# TLV3501.net
KiCad netlist of a schematic drawn in EasyEDA Pro
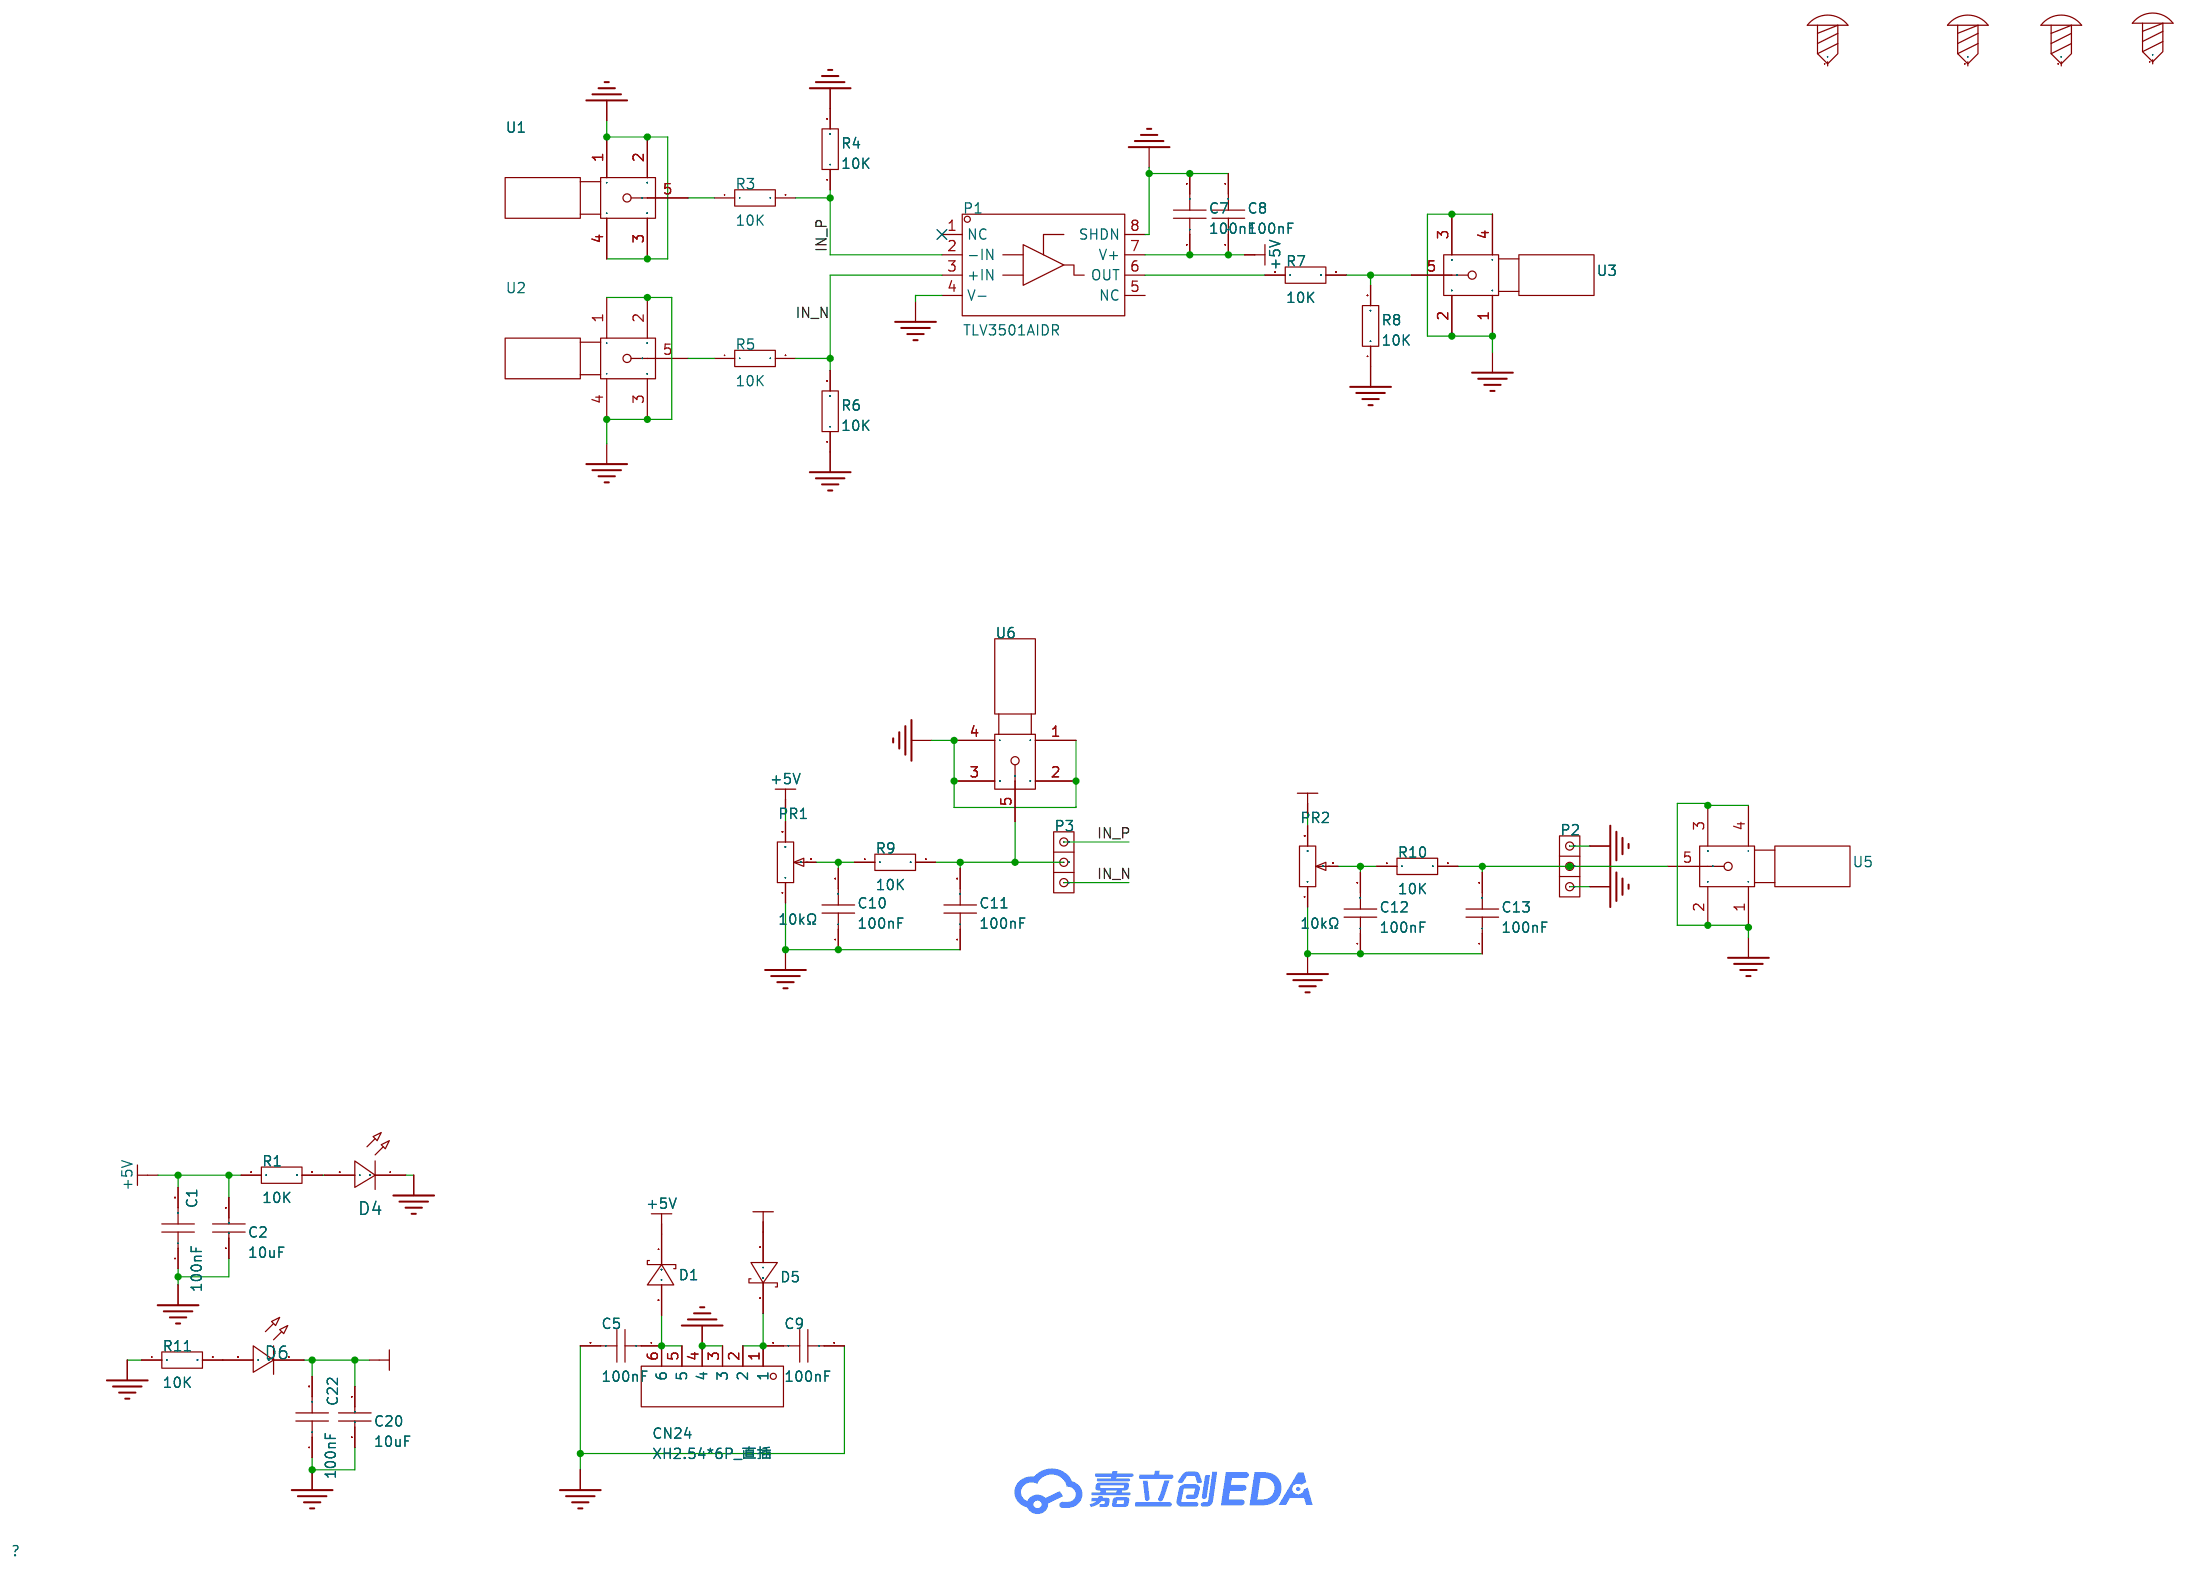
[diagram p0: schematic sheet]

(export (version "E")
  (design (tool "Eeschema 10.0.6"))
  (components
    (comp (ref "C1")
      (value "100nF")
      (footprint "easyedapro:C0805")
      (libsource (lib "easyedapro") (part "CapAcitance"))
    )
    (comp (ref "C2")
      (value "10uF")
      (footprint "easyedapro:C1210")
      (description "容值:10uF;精度:±10%;额定电压:25V;材质(温度系数):X7R;")
      (fields
        (field (name "Manufacturer Part") "CL32B106KAJNNNE")
        (field (name "Manufacturer") "SAMSUNG(三星)")
      )
      (libsource (lib "easyedapro") (part "CL32B106KAJNNNE"))
    )
    (comp (ref "C5")
      (value "100nF")
      (footprint "easyedapro:C0805")
      (libsource (lib "easyedapro") (part "CapAcitance"))
    )
    (comp (ref "C7")
      (value "100nF")
      (footprint "easyedapro:C0805")
      (libsource (lib "easyedapro") (part "CapAcitance"))
    )
    (comp (ref "C8")
      (value "100nF")
      (footprint "easyedapro:C0805")
      (libsource (lib "easyedapro") (part "CapAcitance"))
    )
    (comp (ref "C9")
      (value "100nF")
      (footprint "easyedapro:C0805")
      (libsource (lib "easyedapro") (part "CapAcitance"))
    )
    (comp (ref "C10")
      (value "100nF")
      (footprint "easyedapro:C0805")
      (libsource (lib "easyedapro") (part "CapAcitance"))
    )
    (comp (ref "C11")
      (value "100nF")
      (footprint "easyedapro:C0805")
      (libsource (lib "easyedapro") (part "CapAcitance"))
    )
    (comp (ref "C12")
      (value "100nF")
      (footprint "easyedapro:C0805")
      (libsource (lib "easyedapro") (part "CapAcitance"))
    )
    (comp (ref "C13")
      (value "100nF")
      (footprint "easyedapro:C0805")
      (libsource (lib "easyedapro") (part "CapAcitance"))
    )
    (comp (ref "C20")
      (value "10uF")
      (footprint "easyedapro:C1210")
      (description "容值:10uF;精度:±10%;额定电压:25V;材质(温度系数):X7R;")
      (fields
        (field (name "Manufacturer Part") "CL32B106KAJNNNE")
        (field (name "Manufacturer") "SAMSUNG(三星)")
      )
      (libsource (lib "easyedapro") (part "CL32B106KAJNNNE"))
    )
    (comp (ref "C22")
      (value "100nF")
      (footprint "easyedapro:C0805")
      (libsource (lib "easyedapro") (part "CapAcitance"))
    )
    (comp (ref "CN24")
      (value "XH2.54*6P_直插")
      (footprint "easyedapro:CONN-TH_XH2.54-6P")
      (libsource (lib "easyedapro") (part "XH2.54*6P_直插"))
    )
    (comp (ref "D1")
      (value "SD103AWS")
      (footprint "easyedapro:SOD-323_L1.8-W1.3-LS2.5-RD")
      (description "正向压降(Vf):600mV@200mA;直流反向耐压(Vr):40V;整流电流:350mA;")
      (fields (field (name "Manufacturer") "Hottech(合科泰)"))
      (libsource (lib "easyedapro") (part "SD103AWS_C181207"))
    )
    (comp (ref "D4")
      (value "~")
      (footprint "easyedapro:LED_0805")
      (libsource (lib "easyedapro") (part "LED_R"))
    )
    (comp (ref "D5")
      (value "SD103AWS")
      (footprint "easyedapro:SOD-323_L1.8-W1.3-LS2.5-RD")
      (description "正向压降(Vf):600mV@200mA;直流反向耐压(Vr):40V;整流电流:350mA;")
      (fields (field (name "Manufacturer") "Hottech(合科泰)"))
      (libsource (lib "easyedapro") (part "SD103AWS_C181207"))
    )
    (comp (ref "D6")
      (value "~")
      (footprint "easyedapro:LED_0805")
      (libsource (lib "easyedapro") (part "LED_R"))
    )
    (comp (ref "P1")
      (value "TLV3501AIDR")
      (footprint "easyedapro:SOP-8_L4.9-W3.9-P1.27-LS6.0-BL")
      (description "输入失调电压(Vos):6.5mV;输入偏置电流(Ib):10pA;")
      (fields (field (name "Manufacturer") "TI(德州仪器)"))
      (libsource (lib "easyedapro") (part "TLV3501AIDR"))
    )
    (comp (ref "P2") (value "~") (footprint "easyedapro:1*3跳线") (libsource (lib "easyedapro") (part "1*3跳线")))
    (comp (ref "P3") (value "~") (footprint "easyedapro:1*3跳线") (libsource (lib "easyedapro") (part "1*3跳线")))
    (comp (ref "PR1")
      (value "10kΩ")
      (footprint "easyedapro:R_3296")
      (libsource (lib "easyedapro") (part "R_3296"))
    )
    (comp (ref "PR2")
      (value "10kΩ")
      (footprint "easyedapro:R_3296")
      (libsource (lib "easyedapro") (part "R_3296"))
    )
    (comp (ref "R1") (value "10K") (footprint "easyedapro:R0805") (libsource (lib "easyedapro") (part "电阻")))
    (comp (ref "R3") (value "10K") (footprint "easyedapro:R0805") (libsource (lib "easyedapro") (part "电阻")))
    (comp (ref "R4") (value "10K") (footprint "easyedapro:R0805") (libsource (lib "easyedapro") (part "电阻")))
    (comp (ref "R5") (value "10K") (footprint "easyedapro:R0805") (libsource (lib "easyedapro") (part "电阻")))
    (comp (ref "R6") (value "10K") (footprint "easyedapro:R0805") (libsource (lib "easyedapro") (part "电阻")))
    (comp (ref "R7") (value "10K") (footprint "easyedapro:R0805") (libsource (lib "easyedapro") (part "电阻")))
    (comp (ref "R8") (value "10K") (footprint "easyedapro:R0805") (libsource (lib "easyedapro") (part "电阻")))
    (comp (ref "R9") (value "10K") (footprint "easyedapro:R0805") (libsource (lib "easyedapro") (part "电阻")))
    (comp (ref "R10") (value "10K") (footprint "easyedapro:R0805") (libsource (lib "easyedapro") (part "电阻")))
    (comp (ref "R11") (value "10K") (footprint "easyedapro:R0805") (libsource (lib "easyedapro") (part "电阻")))
    (comp (ref "SCREW1")
      (value "~")
      (footprint "easyedapro:M2螺丝")
      (libsource (lib "easyedapro") (part "螺丝孔"))
    )
    (comp (ref "SCREW2")
      (value "~")
      (footprint "easyedapro:M2螺丝")
      (libsource (lib "easyedapro") (part "螺丝孔"))
    )
    (comp (ref "SCREW3")
      (value "~")
      (footprint "easyedapro:M2螺丝")
      (libsource (lib "easyedapro") (part "螺丝孔"))
    )
    (comp (ref "SCREW4")
      (value "~")
      (footprint "easyedapro:M2螺丝")
      (libsource (lib "easyedapro") (part "螺丝孔"))
    )
    (comp (ref "U1") (value "~") (footprint "easyedapro:SMA") (libsource (lib "easyedapro") (part "SMA")))
    (comp (ref "U2") (value "~") (footprint "easyedapro:SMA") (libsource (lib "easyedapro") (part "SMA")))
    (comp (ref "U3") (value "~") (footprint "easyedapro:SMA") (libsource (lib "easyedapro") (part "SMA")))
    (comp (ref "U5") (value "~") (footprint "easyedapro:SMA") (libsource (lib "easyedapro") (part "SMA")))
    (comp (ref "U6") (value "~") (footprint "easyedapro:SMA") (libsource (lib "easyedapro") (part "SMA")))
  )
  (nets
    (net (code "1") (name "+5V") (class "Default")
      (node (ref "C1") (pin "2") (pinfunction "2_2") (pintype "input"))
      (node (ref "C2") (pin "2") (pinfunction "2_2") (pintype "input"))
      (node (ref "C7") (pin "2") (pinfunction "2_2") (pintype "input"))
      (node (ref "C8") (pin "2") (pinfunction "2_2") (pintype "input"))
      (node (ref "D1") (pin "1") (pinfunction "C_1") (pintype "unspecified"))
      (node (ref "P1") (pin "7") (pinfunction "V+_7") (pintype "unspecified"))
      (node (ref "PR1") (pin "3") (pinfunction "3_3") (pintype "input"))
      (node (ref "R1") (pin "1") (pinfunction "1_1") (pintype "input"))
    )
    (net (code "2") (name "-5V") (class "Default")
      (node (ref "C20") (pin "2") (pinfunction "2_2") (pintype "input"))
      (node (ref "C22") (pin "2") (pinfunction "2_2") (pintype "input"))
      (node (ref "D5") (pin "2") (pinfunction "A_2") (pintype "unspecified"))
      (node (ref "D6") (pin "1") (pinfunction "C_1") (pintype "input"))
      (node (ref "PR2") (pin "3") (pinfunction "3_3") (pintype "input"))
    )
    (net (code "3") (name "/IN_N") (class "Default")
      (node (ref "P1") (pin "3") (pinfunction "+IN_3") (pintype "unspecified"))
      (node (ref "P3") (pin "3") (pinfunction "3_3") (pintype "input"))
      (node (ref "R5") (pin "2") (pinfunction "2_2") (pintype "input"))
      (node (ref "R6") (pin "2") (pinfunction "2_2") (pintype "input"))
    )
    (net (code "4") (name "/IN_P") (class "Default")
      (node (ref "P1") (pin "2") (pinfunction "-IN_2") (pintype "unspecified"))
      (node (ref "P3") (pin "1") (pinfunction "1_1") (pintype "input"))
      (node (ref "R3") (pin "2") (pinfunction "2_2") (pintype "input"))
      (node (ref "R4") (pin "1") (pinfunction "1_1") (pintype "input"))
    )
    (net (code "5") (name "GND") (class "Default")
      (node (ref "C1") (pin "1") (pinfunction "1_1") (pintype "input"))
      (node (ref "C10") (pin "1") (pinfunction "1_1") (pintype "input"))
      (node (ref "C11") (pin "1") (pinfunction "1_1") (pintype "input"))
      (node (ref "C12") (pin "1") (pinfunction "1_1") (pintype "input"))
      (node (ref "C13") (pin "1") (pinfunction "1_1") (pintype "input"))
      (node (ref "C2") (pin "1") (pinfunction "1_1") (pintype "input"))
      (node (ref "C20") (pin "1") (pinfunction "1_1") (pintype "input"))
      (node (ref "C22") (pin "1") (pinfunction "1_1") (pintype "input"))
      (node (ref "C5") (pin "2") (pinfunction "2_2") (pintype "input"))
      (node (ref "C7") (pin "1") (pinfunction "1_1") (pintype "input"))
      (node (ref "C8") (pin "1") (pinfunction "1_1") (pintype "input"))
      (node (ref "C9") (pin "1") (pinfunction "1_1") (pintype "input"))
      (node (ref "CN24") (pin "3") (pinfunction "3_3") (pintype "input"))
      (node (ref "CN24") (pin "4") (pinfunction "4_4") (pintype "input"))
      (node (ref "D4") (pin "1") (pinfunction "C_1") (pintype "input"))
      (node (ref "P1") (pin "4") (pinfunction "V-_4") (pintype "unspecified"))
      (node (ref "P1") (pin "8") (pinfunction "SHDN_8") (pintype "unspecified"))
      (node (ref "P2") (pin "1") (pinfunction "1_1") (pintype "input"))
      (node (ref "P2") (pin "3") (pinfunction "3_3") (pintype "input"))
      (node (ref "PR1") (pin "1") (pinfunction "1_1") (pintype "input"))
      (node (ref "PR2") (pin "1") (pinfunction "1_1") (pintype "input"))
      (node (ref "R11") (pin "1") (pinfunction "1_1") (pintype "input"))
      (node (ref "R4") (pin "2") (pinfunction "2_2") (pintype "input"))
      (node (ref "R6") (pin "1") (pinfunction "1_1") (pintype "input"))
      (node (ref "R8") (pin "1") (pinfunction "1_1") (pintype "input"))
      (node (ref "U1") (pin "1") (pinfunction "1_1") (pintype "input"))
      (node (ref "U1") (pin "2") (pinfunction "2_2") (pintype "input"))
      (node (ref "U1") (pin "3") (pinfunction "3_3") (pintype "input"))
      (node (ref "U1") (pin "4") (pinfunction "4_4") (pintype "input"))
      (node (ref "U2") (pin "1") (pinfunction "1_1") (pintype "input"))
      (node (ref "U2") (pin "2") (pinfunction "2_2") (pintype "input"))
      (node (ref "U2") (pin "3") (pinfunction "3_3") (pintype "input"))
      (node (ref "U2") (pin "4") (pinfunction "4_4") (pintype "input"))
      (node (ref "U3") (pin "1") (pinfunction "1_1") (pintype "input"))
      (node (ref "U3") (pin "2") (pinfunction "2_2") (pintype "input"))
      (node (ref "U3") (pin "3") (pinfunction "3_3") (pintype "input"))
      (node (ref "U3") (pin "4") (pinfunction "4_4") (pintype "input"))
      (node (ref "U5") (pin "1") (pinfunction "1_1") (pintype "input"))
      (node (ref "U5") (pin "2") (pinfunction "2_2") (pintype "input"))
      (node (ref "U5") (pin "3") (pinfunction "3_3") (pintype "input"))
      (node (ref "U5") (pin "4") (pinfunction "4_4") (pintype "input"))
      (node (ref "U6") (pin "1") (pinfunction "1_1") (pintype "input"))
      (node (ref "U6") (pin "2") (pinfunction "2_2") (pintype "input"))
      (node (ref "U6") (pin "3") (pinfunction "3_3") (pintype "input"))
      (node (ref "U6") (pin "4") (pinfunction "4_4") (pintype "input"))
    )
    (net (code "6") (name "Net-(C10-Pad2)") (class "Default")
      (node (ref "C10") (pin "2") (pinfunction "2_2") (pintype "input"))
      (node (ref "PR1") (pin "2") (pinfunction "2_2") (pintype "input"))
      (node (ref "R9") (pin "1") (pinfunction "1_1") (pintype "input"))
    )
    (net (code "7") (name "Net-(C11-Pad2)") (class "Default")
      (node (ref "C11") (pin "2") (pinfunction "2_2") (pintype "input"))
      (node (ref "P3") (pin "2") (pinfunction "2_2") (pintype "input"))
      (node (ref "R9") (pin "2") (pinfunction "2_2") (pintype "input"))
      (node (ref "U6") (pin "5") (pinfunction "5_5") (pintype "input"))
    )
    (net (code "8") (name "Net-(C12-Pad2)") (class "Default")
      (node (ref "C12") (pin "2") (pinfunction "2_2") (pintype "input"))
      (node (ref "PR2") (pin "2") (pinfunction "2_2") (pintype "input"))
      (node (ref "R10") (pin "1") (pinfunction "1_1") (pintype "input"))
    )
    (net (code "9") (name "Net-(C13-Pad2)") (class "Default")
      (node (ref "C13") (pin "2") (pinfunction "2_2") (pintype "input"))
      (node (ref "P2") (pin "2") (pinfunction "2_2") (pintype "input"))
      (node (ref "R10") (pin "2") (pinfunction "2_2") (pintype "input"))
      (node (ref "U5") (pin "5") (pinfunction "5_5") (pintype "input"))
    )
    (net (code "10") (name "Net-(D1-A)") (class "Default")
      (node (ref "C5") (pin "1") (pinfunction "1_1") (pintype "input"))
      (node (ref "CN24") (pin "5") (pinfunction "5_5") (pintype "input"))
      (node (ref "CN24") (pin "6") (pinfunction "6_6") (pintype "input"))
      (node (ref "D1") (pin "2") (pinfunction "A_2") (pintype "unspecified"))
    )
    (net (code "11") (name "Net-(D4-A)") (class "Default")
      (node (ref "D4") (pin "2") (pinfunction "A_2") (pintype "input"))
      (node (ref "R1") (pin "2") (pinfunction "2_2") (pintype "input"))
    )
    (net (code "12") (name "Net-(D5-C)") (class "Default")
      (node (ref "C9") (pin "2") (pinfunction "2_2") (pintype "input"))
      (node (ref "CN24") (pin "1") (pinfunction "1_1") (pintype "input"))
      (node (ref "CN24") (pin "2") (pinfunction "2_2") (pintype "input"))
      (node (ref "D5") (pin "1") (pinfunction "C_1") (pintype "unspecified"))
    )
    (net (code "13") (name "Net-(D6-A)") (class "Default")
      (node (ref "D6") (pin "2") (pinfunction "A_2") (pintype "input"))
      (node (ref "R11") (pin "2") (pinfunction "2_2") (pintype "input"))
    )
    (net (code "14") (name "Net-(P1-OUT)") (class "Default")
      (node (ref "P1") (pin "6") (pinfunction "OUT_6") (pintype "unspecified"))
      (node (ref "R7") (pin "1") (pinfunction "1_1") (pintype "input"))
    )
    (net (code "15") (name "Net-(R3-Pad1)") (class "Default")
      (node (ref "R3") (pin "1") (pinfunction "1_1") (pintype "input"))
      (node (ref "U1") (pin "5") (pinfunction "5_5") (pintype "input"))
    )
    (net (code "16") (name "Net-(R5-Pad1)") (class "Default")
      (node (ref "R5") (pin "1") (pinfunction "1_1") (pintype "input"))
      (node (ref "U2") (pin "5") (pinfunction "5_5") (pintype "input"))
    )
    (net (code "17") (name "Net-(R7-Pad2)") (class "Default")
      (node (ref "R7") (pin "2") (pinfunction "2_2") (pintype "input"))
      (node (ref "R8") (pin "2") (pinfunction "2_2") (pintype "input"))
      (node (ref "U3") (pin "5") (pinfunction "5_5") (pintype "input"))
    )
    (net (code "18") (name "unconnected-(P1-NC-Pad1)") (class "Default")
      (node (ref "P1") (pin "1") (pinfunction "NC_1") (pintype "unspecified+no_connect"))
    )
    (net (code "19") (name "unconnected-(P1-NC-Pad5)") (class "Default")
      (node (ref "P1") (pin "5") (pinfunction "NC_5") (pintype "unspecified"))
    )
    (net (code "20") (name "unconnected-(SCREW1-Pad1)") (class "Default")
      (node (ref "SCREW1") (pin "1") (pinfunction "1_1") (pintype "input"))
    )
    (net (code "21") (name "unconnected-(SCREW2-Pad1)") (class "Default")
      (node (ref "SCREW2") (pin "1") (pinfunction "1_1") (pintype "input"))
    )
    (net (code "22") (name "unconnected-(SCREW3-Pad1)") (class "Default")
      (node (ref "SCREW3") (pin "1") (pinfunction "1_1") (pintype "input"))
    )
    (net (code "23") (name "unconnected-(SCREW4-Pad1)") (class "Default")
      (node (ref "SCREW4") (pin "1") (pinfunction "1_1") (pintype "input"))
    )
  )
)
